# Mikrolysreklamen.net
KiCad netlist of a schematic drawn in Altium Designer
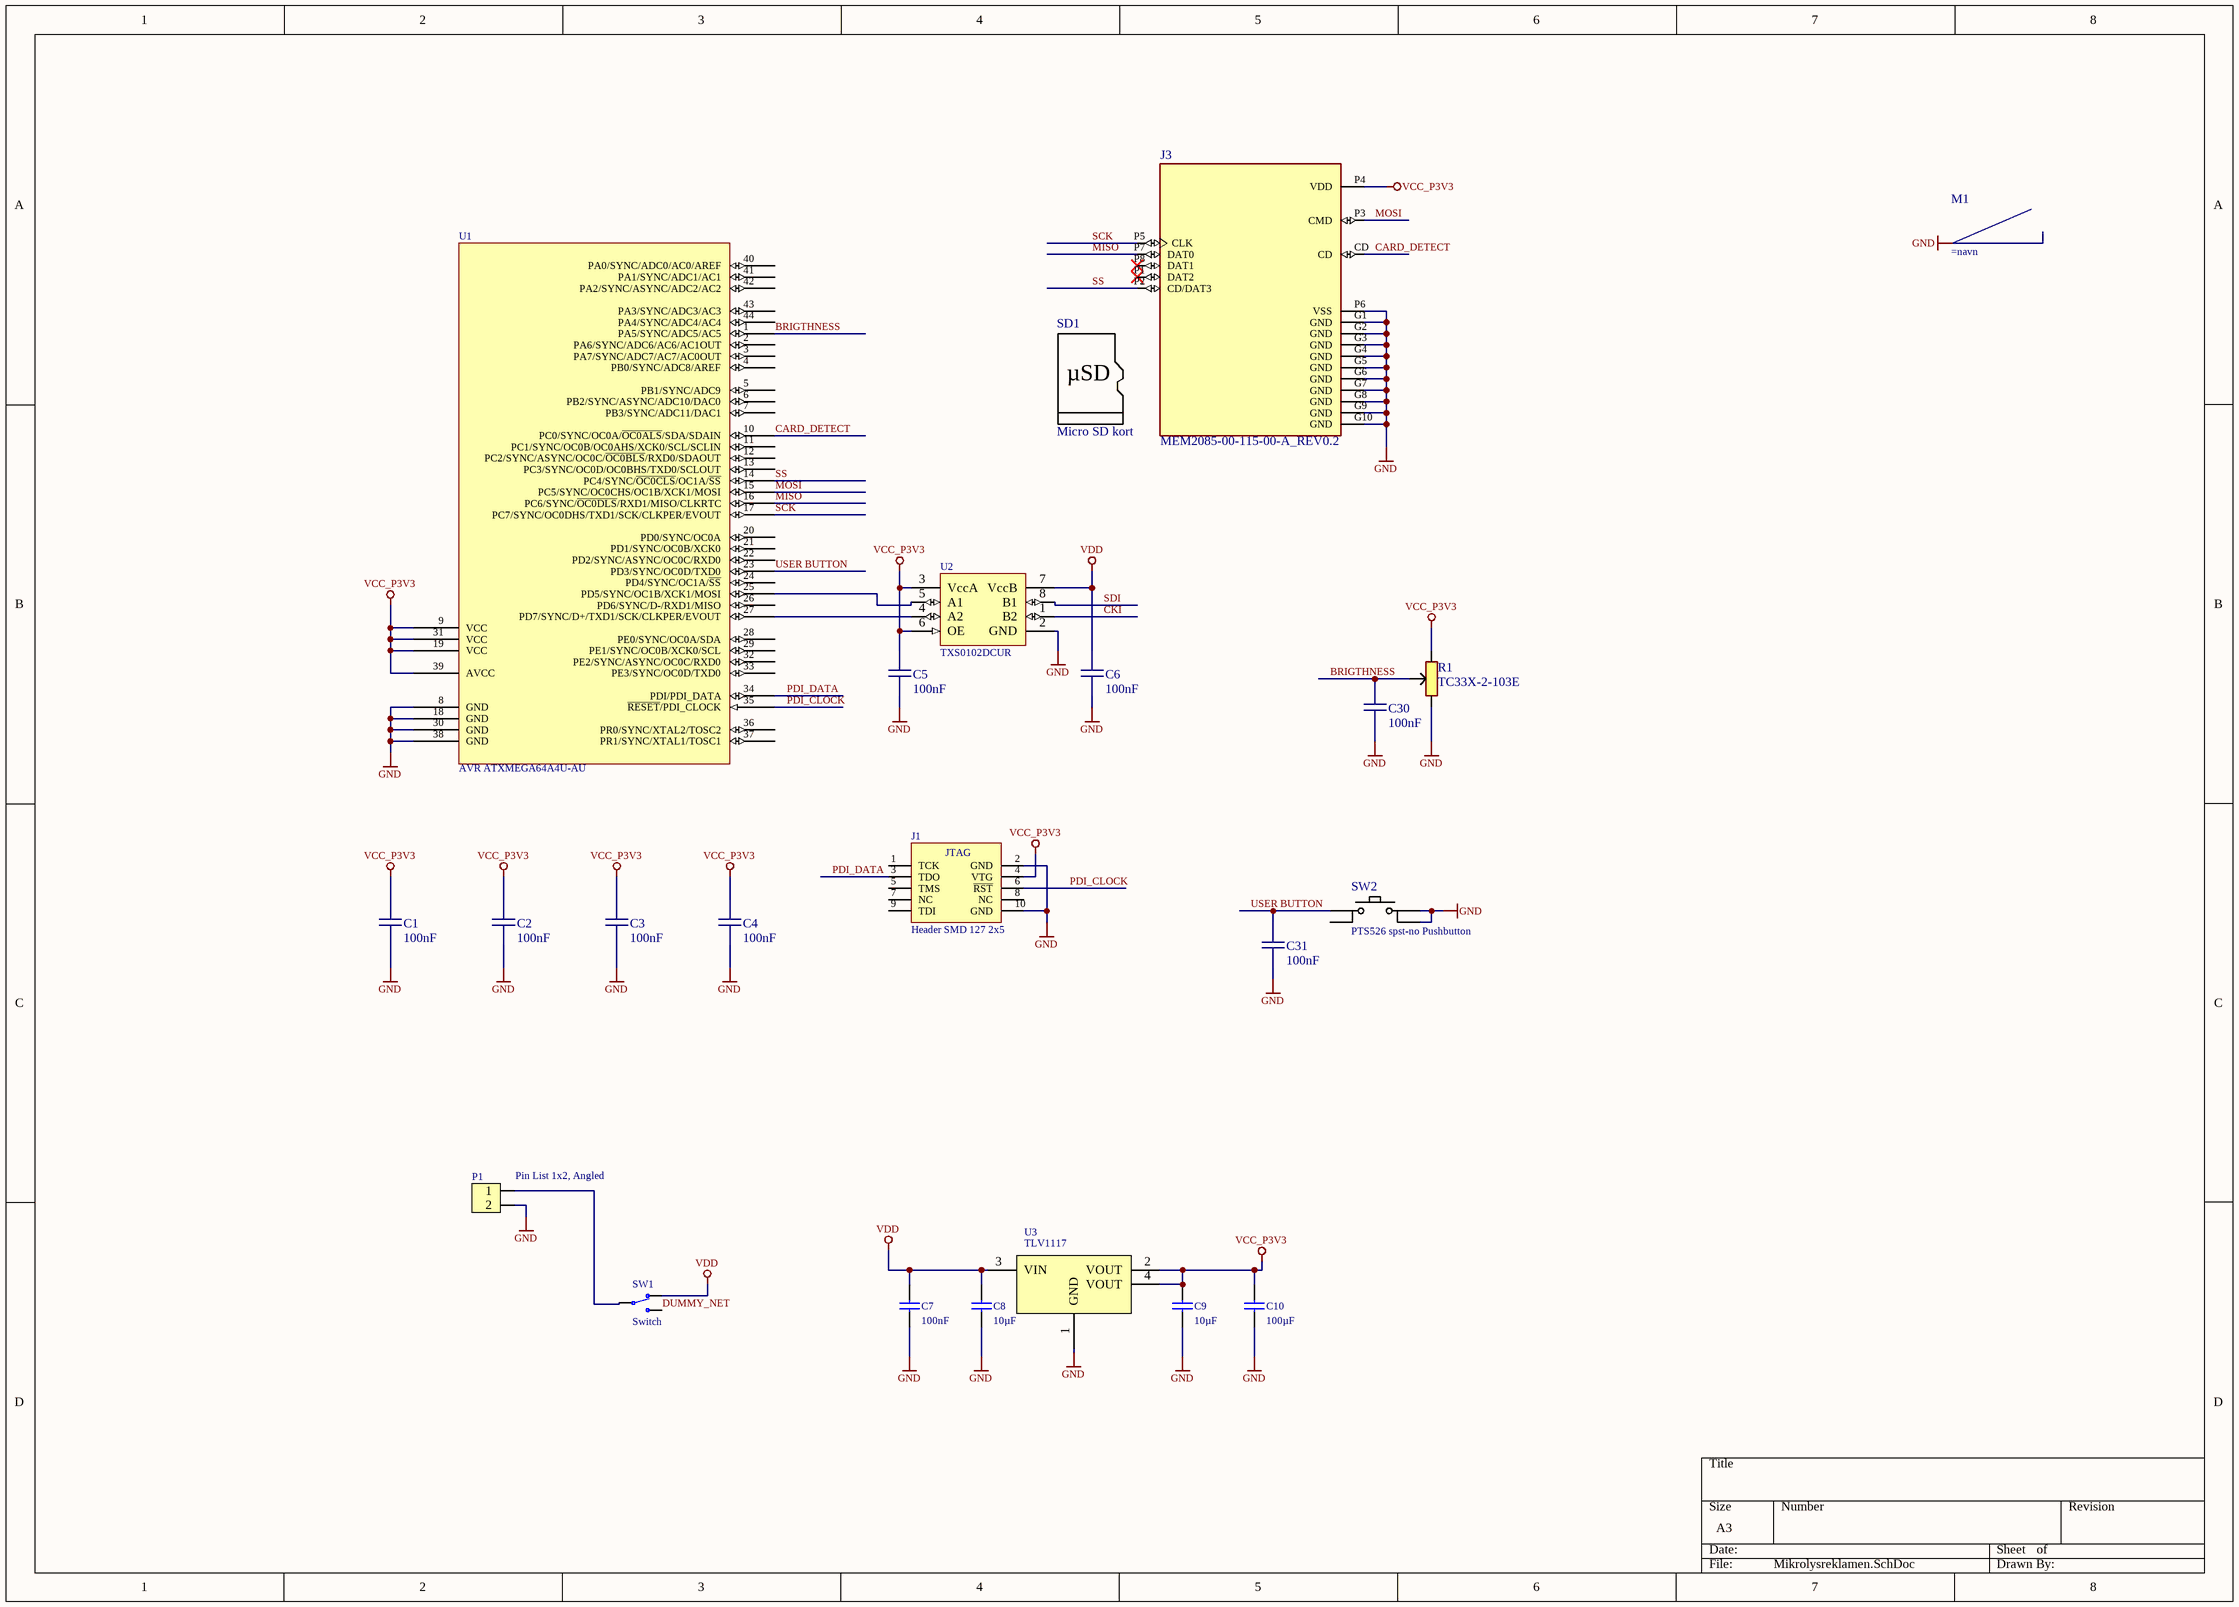
[diagram p0: Mikrolysreklamen.SchDoc]

(export (version "E")
  (design (tool "Eeschema 10.0.6"))
  (components
    (comp (ref "C1")
      (value "100nF")
      (footprint "CAPC0603(1608)55_N")
      (libsource (lib "OVLib_64") (part "CAP"))
    )
    (comp (ref "C2")
      (value "100nF")
      (footprint "CAPC0603(1608)55_N")
      (libsource (lib "OVLib_64") (part "CAP"))
    )
    (comp (ref "C3")
      (value "100nF")
      (footprint "CAPC0603(1608)55_N")
      (libsource (lib "OVLib_64") (part "CAP"))
    )
    (comp (ref "C4")
      (value "100nF")
      (footprint "CAPC0603(1608)55_N")
      (libsource (lib "OVLib_64") (part "CAP"))
    )
    (comp (ref "C5")
      (value "100nF")
      (footprint "CAPC0603(1608)55_N")
      (libsource (lib "OVLib_64") (part "CAP"))
    )
    (comp (ref "C6")
      (value "100nF")
      (footprint "CAPC0603(1608)55_N")
      (libsource (lib "OVLib_64") (part "CAP"))
    )
    (comp (ref "C7")
      (value "100nF")
      (footprint "CAPC1005X04L")
      (description "Capacitor, X7R, ±10%")
      (fields (field (name "PART NUMBER") "C0402-100n") (field (name "PUBLISHER") "Nordic Semiconductor"))
      (libsource (lib "Nordic Passive DB") (part "CAP"))
    )
    (comp (ref "C8")
      (value "10µF")
      (footprint "CAPC1608X06L")
      (description "Capacitor, X5R, ±20%")
      (fields (field (name "PART NUMBER") "C0603-10µ") (field (name "PUBLISHER") "Nordic Semiconductor"))
      (libsource (lib "Nordic Passive DB") (part "CAP"))
    )
    (comp (ref "C9")
      (value "10µF")
      (footprint "CAPC1608X06L")
      (description "Capacitor, X5R, ±20%")
      (fields (field (name "PART NUMBER") "C0603-10µ") (field (name "PUBLISHER") "Nordic Semiconductor"))
      (libsource (lib "Nordic Passive DB") (part "CAP"))
    )
    (comp (ref "C10")
      (value "100µF")
      (footprint "CAPC2012X11L")
      (description "Chip Cap 0805")
      (fields (field (name "PART NUMBER") "C0805-TBD") (field (name "PUBLISHER") "Nordic Semiconductor"))
      (libsource (lib "Nordic Passive DB") (part "CAP"))
    )
    (comp (ref "C30")
      (value "100nF")
      (footprint "CAPC0603(1608)55_N")
      (libsource (lib "OVLib_64") (part "CAP"))
    )
    (comp (ref "C31")
      (value "100nF")
      (footprint "CAPC0603(1608)55_N")
      (libsource (lib "OVLib_64") (part "CAP"))
    )
    (comp (ref "J1")
      (value "Header SMD 127 2x5")
      (footprint "SMDHDRV10P127_2X5_615X330X560B")
      (description "1,27mm Pitch SMD Header")
      (libsource (lib "OVLib") (part "AVRJTAG"))
    )
    (comp (ref "J3")
      (value "MEM2085-00-115-00-A_REV0.2")
      (footprint "GCT_MEM2085-00-115-00-A_REV0.2")
      (description "MicroSD Push pull Memory Card Connector")
      (fields (field (name "MP") "MEM2085-00-115-00-A") (field (name "MF") "Global Connector Technology"))
      (libsource (lib "OVLib_64") (part "MEM2085-00-115-00-A_REV0.2"))
    )
    (comp (ref "M1")
      (value "~")
      (footprint "Imponatornaal_liten")
      (libsource (lib "Imponatornaal") (part "Imponatornaal"))
    )
    (comp (ref "P1")
      (value "Pin List 1x2, Angled")
      (footprint "LIST_ANG_1x2-SMD-2.54MM")
      (description "Pin List 1x2, 2.54mm (100mil), Right Angled, SMD")
      (fields
        (field (name "PART NUMBER") "Pin List Ang 1x2 SMD, 2.54mm")
        (field (name "MANUFACTURER") "W-CON")
        (field (name "PUBLISHER") "Nordic Semiconductor")
      )
      (libsource (lib "Nordic Passive DB") (part "CONN-2"))
    )
    (comp (ref "R1")
      (value "TC33X-2-103E")
      (footprint "TRIM_TC33X-2-103E")
      (libsource (lib "OVLib_64") (part "Potmeter"))
    )
    (comp (ref "SD1")
      (value "Micro SD kort")
      (footprint "microsdcard")
      (libsource (lib "OVLib_64") (part "microsdcard"))
    )
    (comp (ref "SW1")
      (value "Switch")
      (footprint "JS102011SAQN")
      (description "SMD slide Switch (ON-ON)")
      (fields
        (field (name "PART NUMBER") "JS102011SAQN")
        (field (name "MANUFACTURER") "C&K Components")
        (field (name "PUBLISHER") "Nordic Semiconductor")
      )
      (libsource (lib "Nordic Discrete DB") (part "SW-SPDT"))
    )
    (comp (ref "SW2")
      (value "PTS526 spst-no Pushbutton")
      (footprint "PTS526_SK15_SMTR2_LFS")
      (libsource (lib "OVLib_64") (part "Pushbutton"))
    )
    (comp (ref "U1")
      (value "AVR ATXMEGA64A4U-AU")
      (footprint "TQFP80P1200X1200X120-44N")
      (description "Mikrokontroller")
      (libsource (lib "OVLib") (part "ATXMEGA-A4U"))
    )
    (comp (ref "U2")
      (value "TXS0102DCUR")
      (footprint "TSSOP50P310X90-8N")
      (description "IC VOLT-LEVEL TRANSLATOR 8-US8")
      (fields
        (field (name "MANUFACTURER") "Texas Instruments")
        (field (name "PUBLISHER") "Nordic Semiconductor")
      )
      (libsource (lib "Nordic Active DB") (part "TXS0102DC"))
    )
    (comp (ref "U3")
      (value "TLV1117")
      (footprint "SOT230P700X180-4N")
      (description "REG LDO 3.3V 0.8A SOT223")
      (fields
        (field (name "PART NUMBER") "TLV1117-33CDCYR")
        (field (name "MANUFACTURER") "Texas Instruments")
        (field (name "PUBLISHER") "Nordic Semiconductor")
      )
      (libsource (lib "Nordic Active DB") (part "LD1117_fixed"))
    )
  )
  (nets
    (net (code "1") (name "/BRIGTHNESS") (class "Default")
      (node (ref "C30") (pin "2") (pinfunction "2_2") (pintype "passive"))
      (node (ref "R1") (pin "2") (pinfunction "2_2") (pintype "passive"))
      (node (ref "U1") (pin "1") (pinfunction "PA5/SYNC/ADC5/AC5_1") (pintype "bidirectional"))
    )
    (net (code "2") (name "/CARD_DETECT") (class "Default")
      (node (ref "J3") (pin "CD") (pinfunction "CD_CD") (pintype "bidirectional"))
      (node (ref "U1") (pin "10") (pinfunction "PC0/SYNC/OC0A/~{OC0ALS}/SDA/SDAIN_10") (pintype "bidirectional"))
    )
    (net (code "3") (name "/CKI") (class "Default")
      (node (ref "U2") (pin "1") (pinfunction "B2_1") (pintype "bidirectional"))
    )
    (net (code "4") (name "/DUMMY_NET") (class "Default")
      (node (ref "SW1") (pin "3") (pinfunction "N.O_3") (pintype "passive"))
    )
    (net (code "5") (name "/MISO") (class "Default")
      (node (ref "J3") (pin "P7") (pinfunction "DAT0_P7") (pintype "bidirectional"))
      (node (ref "U1") (pin "16") (pinfunction "PC6/SYNC/~{OC0DLS}/RXD1/MISO/CLKRTC_16") (pintype "bidirectional"))
    )
    (net (code "6") (name "/MOSI") (class "Default")
      (node (ref "J3") (pin "P3") (pinfunction "CMD_P3") (pintype "bidirectional"))
      (node (ref "U1") (pin "15") (pinfunction "PC5/SYNC/OC0CHS/OC1B/XCK1/MOSI_15") (pintype "bidirectional"))
    )
    (net (code "7") (name "/PDI_CLOCK") (class "Default")
      (node (ref "J1") (pin "6") (pinfunction "~{RST}_6") (pintype "passive"))
      (node (ref "U1") (pin "35") (pinfunction "~{RESET}/PDI_CLOCK_35") (pintype "input"))
    )
    (net (code "8") (name "/PDI_DATA") (class "Default")
      (node (ref "J1") (pin "3") (pinfunction "TDO_3") (pintype "passive"))
      (node (ref "U1") (pin "34") (pinfunction "PDI/PDI_DATA_34") (pintype "bidirectional"))
    )
    (net (code "9") (name "/SCK") (class "Default")
      (node (ref "J3") (pin "P5") (pinfunction "CLK_P5") (pintype "bidirectional"))
      (node (ref "U1") (pin "17") (pinfunction "PC7/SYNC/OC0DHS/TXD1/SCK/CLKPER/EVOUT_17") (pintype "bidirectional"))
    )
    (net (code "10") (name "/SDI") (class "Default")
      (node (ref "U2") (pin "8") (pinfunction "B1_8") (pintype "bidirectional"))
    )
    (net (code "11") (name "/SS") (class "Default")
      (node (ref "J3") (pin "P2") (pinfunction "CD/DAT3_P2") (pintype "bidirectional"))
      (node (ref "U1") (pin "14") (pinfunction "PC4/SYNC/~{OC0CLS}/OC1A/~{SS}_14") (pintype "bidirectional"))
    )
    (net (code "12") (name "/USER BUTTON") (class "Default")
      (node (ref "C31") (pin "2") (pinfunction "2_2") (pintype "passive"))
      (node (ref "SW2") (pin "1") (pinfunction "1_1") (pintype "passive"))
      (node (ref "U1") (pin "23") (pinfunction "PD3/SYNC/OC0D/TXD0_23") (pintype "bidirectional"))
    )
    (net (code "13") (name "GND") (class "Default")
      (node (ref "C1") (pin "1") (pinfunction "1_1") (pintype "passive"))
      (node (ref "C10") (pin "1") (pinfunction "1_1") (pintype "passive"))
      (node (ref "C2") (pin "1") (pinfunction "1_1") (pintype "passive"))
      (node (ref "C3") (pin "1") (pinfunction "1_1") (pintype "passive"))
      (node (ref "C30") (pin "1") (pinfunction "1_1") (pintype "passive"))
      (node (ref "C31") (pin "1") (pinfunction "1_1") (pintype "passive"))
      (node (ref "C4") (pin "1") (pinfunction "1_1") (pintype "passive"))
      (node (ref "C5") (pin "1") (pinfunction "1_1") (pintype "passive"))
      (node (ref "C6") (pin "1") (pinfunction "1_1") (pintype "passive"))
      (node (ref "C7") (pin "1") (pinfunction "1_1") (pintype "passive"))
      (node (ref "C8") (pin "1") (pinfunction "1_1") (pintype "passive"))
      (node (ref "C9") (pin "1") (pinfunction "1_1") (pintype "passive"))
      (node (ref "J1") (pin "10") (pinfunction "GND_10") (pintype "passive"))
      (node (ref "J1") (pin "2") (pinfunction "GND_2") (pintype "passive"))
      (node (ref "J3") (pin "G1") (pinfunction "GND_G1") (pintype "power_in"))
      (node (ref "J3") (pin "G10") (pinfunction "GND_G10") (pintype "power_in"))
      (node (ref "J3") (pin "G2") (pinfunction "GND_G2") (pintype "power_in"))
      (node (ref "J3") (pin "G3") (pinfunction "GND_G3") (pintype "power_in"))
      (node (ref "J3") (pin "G4") (pinfunction "GND_G4") (pintype "power_in"))
      (node (ref "J3") (pin "G5") (pinfunction "GND_G5") (pintype "power_in"))
      (node (ref "J3") (pin "G6") (pinfunction "GND_G6") (pintype "power_in"))
      (node (ref "J3") (pin "G7") (pinfunction "GND_G7") (pintype "power_in"))
      (node (ref "J3") (pin "G8") (pinfunction "GND_G8") (pintype "power_in"))
      (node (ref "J3") (pin "G9") (pinfunction "GND_G9") (pintype "power_in"))
      (node (ref "J3") (pin "P6") (pinfunction "VSS_P6") (pintype "power_in"))
      (node (ref "M1") (pin "0") (pinfunction "0_0") (pintype "passive"))
      (node (ref "P1") (pin "2") (pinfunction "2_2") (pintype "passive"))
      (node (ref "R1") (pin "1") (pinfunction "1_1") (pintype "passive"))
      (node (ref "SW2") (pin "3") (pinfunction "3_3") (pintype "passive"))
      (node (ref "SW2") (pin "4") (pinfunction "4_4") (pintype "passive"))
      (node (ref "U1") (pin "18") (pinfunction "GND_18") (pintype "power_in"))
      (node (ref "U1") (pin "30") (pinfunction "GND_30") (pintype "power_in"))
      (node (ref "U1") (pin "38") (pinfunction "GND_38") (pintype "power_in"))
      (node (ref "U1") (pin "8") (pinfunction "GND_8") (pintype "power_in"))
      (node (ref "U2") (pin "2") (pinfunction "GND_2") (pintype "power_in"))
      (node (ref "U3") (pin "1") (pinfunction "GND_1") (pintype "power_in"))
    )
    (net (code "14") (name "Net-(SW1-COM)") (class "Default")
      (node (ref "P1") (pin "1") (pinfunction "1_1") (pintype "passive"))
      (node (ref "SW1") (pin "2") (pinfunction "COM_2") (pintype "passive"))
    )
    (net (code "15") (name "Net-(U1-PD5{slash}SYNC{slash}OC1B{slash}XCK1{slash}MOSI)") (class "Default")
      (node (ref "U1") (pin "25") (pinfunction "PD5/SYNC/OC1B/XCK1/MOSI_25") (pintype "bidirectional"))
      (node (ref "U2") (pin "5") (pinfunction "A1_5") (pintype "bidirectional"))
    )
    (net (code "16") (name "Net-(U1-PD7{slash}SYNC{slash}D+{slash}TXD1{slash}SCK{slash}CLKPER{slash}EVOUT)") (class "Default")
      (node (ref "U1") (pin "27") (pinfunction "PD7/SYNC/D+/TXD1/SCK/CLKPER/EVOUT_27") (pintype "bidirectional"))
      (node (ref "U2") (pin "4") (pinfunction "A2_4") (pintype "bidirectional"))
    )
    (net (code "17") (name "VCC_P3V3") (class "Default")
      (node (ref "C1") (pin "2") (pinfunction "2_2") (pintype "passive"))
      (node (ref "C10") (pin "2") (pinfunction "2_2") (pintype "passive"))
      (node (ref "C2") (pin "2") (pinfunction "2_2") (pintype "passive"))
      (node (ref "C3") (pin "2") (pinfunction "2_2") (pintype "passive"))
      (node (ref "C4") (pin "2") (pinfunction "2_2") (pintype "passive"))
      (node (ref "C5") (pin "2") (pinfunction "2_2") (pintype "passive"))
      (node (ref "C9") (pin "2") (pinfunction "2_2") (pintype "passive"))
      (node (ref "J1") (pin "4") (pinfunction "VTG_4") (pintype "passive"))
      (node (ref "J3") (pin "P4") (pinfunction "VDD_P4") (pintype "power_in"))
      (node (ref "R1") (pin "3") (pinfunction "3_3") (pintype "passive"))
      (node (ref "U1") (pin "19") (pinfunction "VCC_19") (pintype "power_in"))
      (node (ref "U1") (pin "31") (pinfunction "VCC_31") (pintype "power_in"))
      (node (ref "U1") (pin "39") (pinfunction "AVCC_39") (pintype "power_in"))
      (node (ref "U1") (pin "9") (pinfunction "VCC_9") (pintype "power_in"))
      (node (ref "U2") (pin "3") (pinfunction "VccA_3") (pintype "power_in"))
      (node (ref "U2") (pin "6") (pinfunction "OE_6") (pintype "input"))
      (node (ref "U3") (pin "2") (pinfunction "VOUT_2") (pintype "power_in"))
      (node (ref "U3") (pin "4") (pinfunction "VOUT_4") (pintype "power_in"))
    )
    (net (code "18") (name "VDD") (class "Default")
      (node (ref "C6") (pin "2") (pinfunction "2_2") (pintype "passive"))
      (node (ref "C7") (pin "2") (pinfunction "2_2") (pintype "passive"))
      (node (ref "C8") (pin "2") (pinfunction "2_2") (pintype "passive"))
      (node (ref "SW1") (pin "1") (pinfunction "N.C_1") (pintype "passive"))
      (node (ref "U2") (pin "7") (pinfunction "VccB_7") (pintype "power_in"))
      (node (ref "U3") (pin "3") (pinfunction "VIN_3") (pintype "power_in"))
    )
    (net (code "19") (name "unconnected-(J1-NC-Pad7)") (class "Default")
      (node (ref "J1") (pin "7") (pinfunction "NC_7") (pintype "passive"))
    )
    (net (code "20") (name "unconnected-(J1-NC-Pad8)") (class "Default")
      (node (ref "J1") (pin "8") (pinfunction "NC_8") (pintype "passive"))
    )
    (net (code "21") (name "unconnected-(J1-TCK-Pad1)") (class "Default")
      (node (ref "J1") (pin "1") (pinfunction "TCK_1") (pintype "passive"))
    )
    (net (code "22") (name "unconnected-(J1-TDI-Pad9)") (class "Default")
      (node (ref "J1") (pin "9") (pinfunction "TDI_9") (pintype "passive"))
    )
    (net (code "23") (name "unconnected-(J1-TMS-Pad5)") (class "Default")
      (node (ref "J1") (pin "5") (pinfunction "TMS_5") (pintype "passive"))
    )
    (net (code "24") (name "unconnected-(J3-DAT1-PadP8)") (class "Default")
      (node (ref "J3") (pin "P8") (pinfunction "DAT1_P8") (pintype "bidirectional+no_connect"))
    )
    (net (code "25") (name "unconnected-(J3-DAT2-PadP1)") (class "Default")
      (node (ref "J3") (pin "P1") (pinfunction "DAT2_P1") (pintype "bidirectional+no_connect"))
    )
    (net (code "26") (name "unconnected-(SW2-Pad2)") (class "Default")
      (node (ref "SW2") (pin "2") (pinfunction "2_2") (pintype "passive"))
    )
    (net (code "27") (name "unconnected-(U1-PA0{slash}SYNC{slash}ADC0{slash}AC0{slash}AREF-Pad40)") (class "Default")
      (node (ref "U1") (pin "40") (pinfunction "PA0/SYNC/ADC0/AC0/AREF_40") (pintype "bidirectional"))
    )
    (net (code "28") (name "unconnected-(U1-PA1{slash}SYNC{slash}ADC1{slash}AC1-Pad41)") (class "Default")
      (node (ref "U1") (pin "41") (pinfunction "PA1/SYNC/ADC1/AC1_41") (pintype "bidirectional"))
    )
    (net (code "29") (name "unconnected-(U1-PA2{slash}SYNC{slash}ASYNC{slash}ADC2{slash}AC2-Pad42)") (class "Default")
      (node (ref "U1") (pin "42") (pinfunction "PA2/SYNC/ASYNC/ADC2/AC2_42") (pintype "bidirectional"))
    )
    (net (code "30") (name "unconnected-(U1-PA3{slash}SYNC{slash}ADC3{slash}AC3-Pad43)") (class "Default")
      (node (ref "U1") (pin "43") (pinfunction "PA3/SYNC/ADC3/AC3_43") (pintype "bidirectional"))
    )
    (net (code "31") (name "unconnected-(U1-PA4{slash}SYNC{slash}ADC4{slash}AC4-Pad44)") (class "Default")
      (node (ref "U1") (pin "44") (pinfunction "PA4/SYNC/ADC4/AC4_44") (pintype "bidirectional"))
    )
    (net (code "32") (name "unconnected-(U1-PA6{slash}SYNC{slash}ADC6{slash}AC6{slash}AC1OUT-Pad2)") (class "Default")
      (node (ref "U1") (pin "2") (pinfunction "PA6/SYNC/ADC6/AC6/AC1OUT_2") (pintype "bidirectional"))
    )
    (net (code "33") (name "unconnected-(U1-PA7{slash}SYNC{slash}ADC7{slash}AC7{slash}AC0OUT-Pad3)") (class "Default")
      (node (ref "U1") (pin "3") (pinfunction "PA7/SYNC/ADC7/AC7/AC0OUT_3") (pintype "bidirectional"))
    )
    (net (code "34") (name "unconnected-(U1-PB0{slash}SYNC{slash}ADC8{slash}AREF-Pad4)") (class "Default")
      (node (ref "U1") (pin "4") (pinfunction "PB0/SYNC/ADC8/AREF_4") (pintype "bidirectional"))
    )
    (net (code "35") (name "unconnected-(U1-PB1{slash}SYNC{slash}ADC9-Pad5)") (class "Default")
      (node (ref "U1") (pin "5") (pinfunction "PB1/SYNC/ADC9_5") (pintype "bidirectional"))
    )
    (net (code "36") (name "unconnected-(U1-PB2{slash}SYNC{slash}ASYNC{slash}ADC10{slash}DAC0-Pad6)") (class "Default")
      (node (ref "U1") (pin "6") (pinfunction "PB2/SYNC/ASYNC/ADC10/DAC0_6") (pintype "bidirectional"))
    )
    (net (code "37") (name "unconnected-(U1-PB3{slash}SYNC{slash}ADC11{slash}DAC1-Pad7)") (class "Default")
      (node (ref "U1") (pin "7") (pinfunction "PB3/SYNC/ADC11/DAC1_7") (pintype "bidirectional"))
    )
    (net (code "38") (name "unconnected-(U1-PC1{slash}SYNC{slash}OC0B{slash}OC0AHS{slash}XCK0{slash}SCL{slash}SCLIN-Pad11)") (class "Default")
      (node (ref "U1") (pin "11") (pinfunction "PC1/SYNC/OC0B/OC0AHS/XCK0/SCL/SCLIN_11") (pintype "bidirectional"))
    )
    (net (code "39") (name "unconnected-(U1-PC2{slash}SYNC{slash}ASYNC{slash}OC0C{slash}~{OC0BLS}{slash}RXD0{slash}SDAOUT-Pad12)") (class "Default")
      (node (ref "U1") (pin "12") (pinfunction "PC2/SYNC/ASYNC/OC0C/~{OC0BLS}/RXD0/SDAOUT_12") (pintype "bidirectional"))
    )
    (net (code "40") (name "unconnected-(U1-PC3{slash}SYNC{slash}OC0D{slash}OC0BHS{slash}TXD0{slash}SCLOUT-Pad13)") (class "Default")
      (node (ref "U1") (pin "13") (pinfunction "PC3/SYNC/OC0D/OC0BHS/TXD0/SCLOUT_13") (pintype "bidirectional"))
    )
    (net (code "41") (name "unconnected-(U1-PD0{slash}SYNC{slash}OC0A-Pad20)") (class "Default")
      (node (ref "U1") (pin "20") (pinfunction "PD0/SYNC/OC0A_20") (pintype "bidirectional"))
    )
    (net (code "42") (name "unconnected-(U1-PD1{slash}SYNC{slash}OC0B{slash}XCK0-Pad21)") (class "Default")
      (node (ref "U1") (pin "21") (pinfunction "PD1/SYNC/OC0B/XCK0_21") (pintype "bidirectional"))
    )
    (net (code "43") (name "unconnected-(U1-PD2{slash}SYNC{slash}ASYNC{slash}OC0C{slash}RXD0-Pad22)") (class "Default")
      (node (ref "U1") (pin "22") (pinfunction "PD2/SYNC/ASYNC/OC0C/RXD0_22") (pintype "bidirectional"))
    )
    (net (code "44") (name "unconnected-(U1-PD4{slash}SYNC{slash}OC1A{slash}~{SS}-Pad24)") (class "Default")
      (node (ref "U1") (pin "24") (pinfunction "PD4/SYNC/OC1A/~{SS}_24") (pintype "bidirectional"))
    )
    (net (code "45") (name "unconnected-(U1-PD6{slash}SYNC{slash}D-{slash}RXD1{slash}MISO-Pad26)") (class "Default")
      (node (ref "U1") (pin "26") (pinfunction "PD6/SYNC/D-/RXD1/MISO_26") (pintype "bidirectional"))
    )
    (net (code "46") (name "unconnected-(U1-PE0{slash}SYNC{slash}OC0A{slash}SDA-Pad28)") (class "Default")
      (node (ref "U1") (pin "28") (pinfunction "PE0/SYNC/OC0A/SDA_28") (pintype "bidirectional"))
    )
    (net (code "47") (name "unconnected-(U1-PE1{slash}SYNC{slash}OC0B{slash}XCK0{slash}SCL-Pad29)") (class "Default")
      (node (ref "U1") (pin "29") (pinfunction "PE1/SYNC/OC0B/XCK0/SCL_29") (pintype "bidirectional"))
    )
    (net (code "48") (name "unconnected-(U1-PE2{slash}SYNC{slash}ASYNC{slash}OC0C{slash}RXD0-Pad32)") (class "Default")
      (node (ref "U1") (pin "32") (pinfunction "PE2/SYNC/ASYNC/OC0C/RXD0_32") (pintype "bidirectional"))
    )
    (net (code "49") (name "unconnected-(U1-PE3{slash}SYNC{slash}OC0D{slash}TXD0-Pad33)") (class "Default")
      (node (ref "U1") (pin "33") (pinfunction "PE3/SYNC/OC0D/TXD0_33") (pintype "bidirectional"))
    )
    (net (code "50") (name "unconnected-(U1-PR0{slash}SYNC{slash}XTAL2{slash}TOSC2-Pad36)") (class "Default")
      (node (ref "U1") (pin "36") (pinfunction "PR0/SYNC/XTAL2/TOSC2_36") (pintype "bidirectional"))
    )
    (net (code "51") (name "unconnected-(U1-PR1{slash}SYNC{slash}XTAL1{slash}TOSC1-Pad37)") (class "Default")
      (node (ref "U1") (pin "37") (pinfunction "PR1/SYNC/XTAL1/TOSC1_37") (pintype "bidirectional"))
    )
  )
)
